# SupplyBoard.net
KiCad netlist of a schematic drawn in Altium Designer
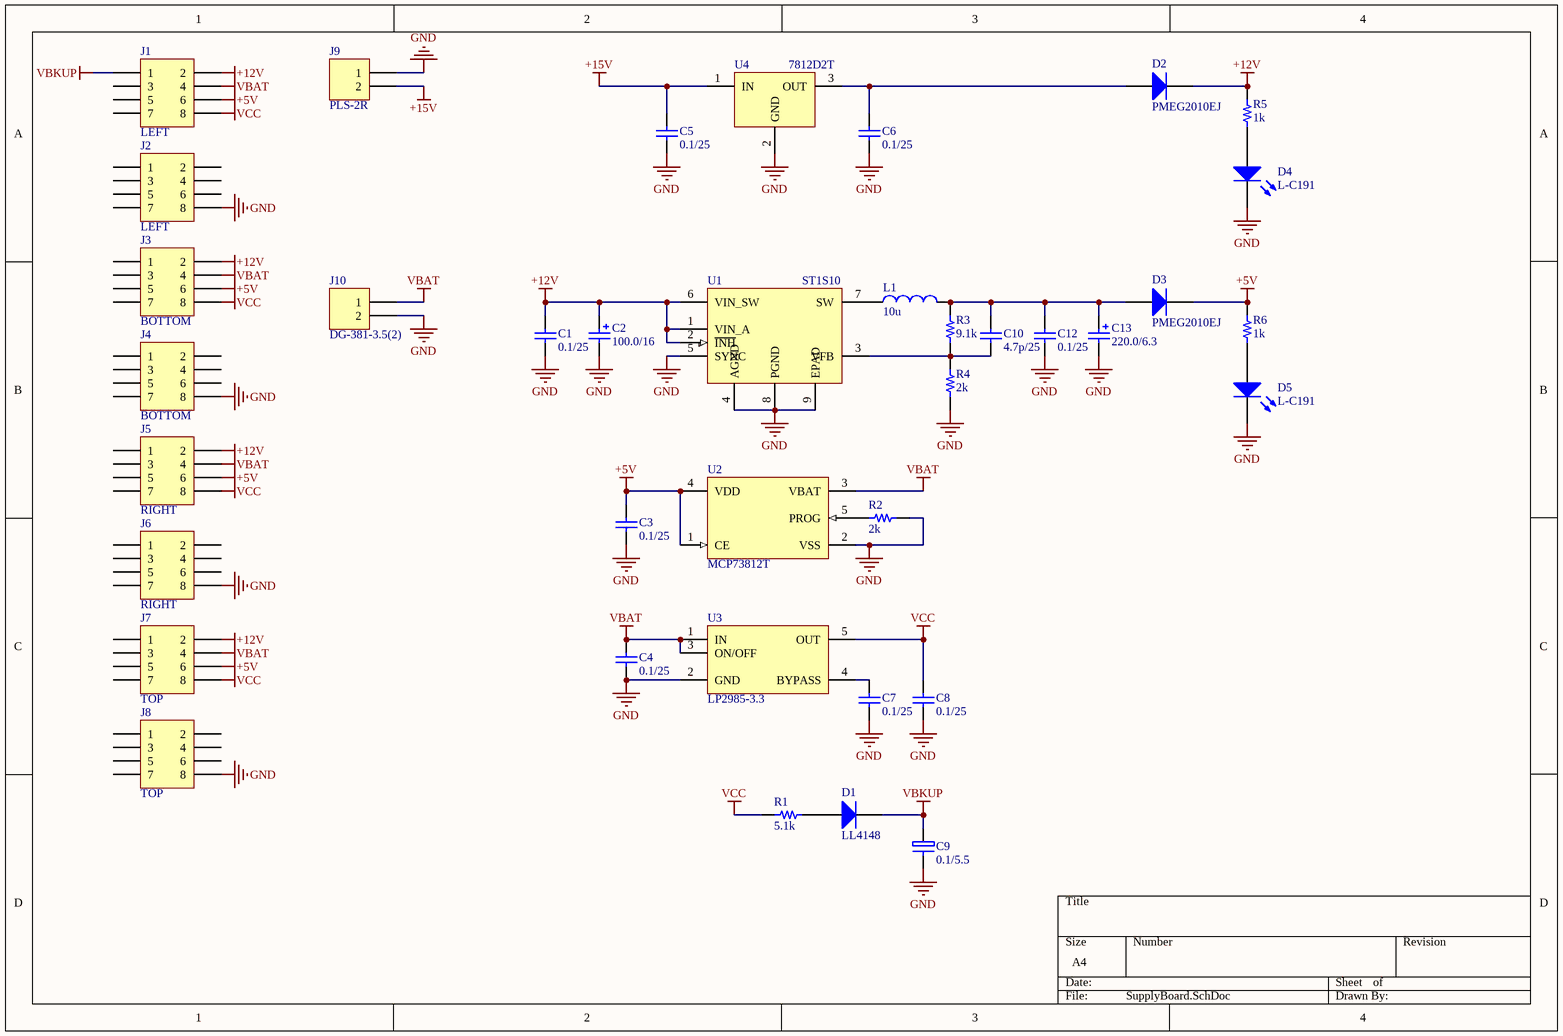
[diagram p0: SupplyBoard.SchDoc]

(export (version "E")
  (design (tool "Eeschema 10.0.6"))
  (components
    (comp (ref "C1")
      (value "0.1/25")
      (footprint "CAP0402")
      (description "Ceramic chip capacitor 0402")
      (fields
        (field (name "PARTNUMBER") "CAP0402")
        (field (name "VOLTAGE") "25")
        (field (name "AUTHOR") "oiezhov")
      )
      (libsource (lib "Library") (part "Capacitor"))
    )
    (comp (ref "C2")
      (value "100.0/16")
      (footprint "SMB")
      (description "Standard tantalum SMT capacitor, size B")
      (fields
        (field (name "PARTNUMBER") "TAJB")
        (field (name "VOLTAGE") "16")
        (field (name "AUTHOR") "oiezhov")
      )
      (libsource (lib "Library") (part "Polar capacitor"))
    )
    (comp (ref "C3")
      (value "0.1/25")
      (footprint "CAP0402")
      (description "Ceramic chip capacitor 0402")
      (fields
        (field (name "PARTNUMBER") "CAP0402")
        (field (name "VOLTAGE") "25")
        (field (name "AUTHOR") "oiezhov")
      )
      (libsource (lib "Library") (part "Capacitor"))
    )
    (comp (ref "C4")
      (value "0.1/25")
      (footprint "CAP0402")
      (description "Ceramic chip capacitor 0402")
      (fields
        (field (name "PARTNUMBER") "CAP0402")
        (field (name "VOLTAGE") "25")
        (field (name "AUTHOR") "oiezhov")
      )
      (libsource (lib "Library") (part "Capacitor"))
    )
    (comp (ref "C5")
      (value "0.1/25")
      (footprint "CAP0402")
      (description "Ceramic chip capacitor 0402")
      (fields
        (field (name "PARTNUMBER") "CAP0402")
        (field (name "VOLTAGE") "25")
        (field (name "AUTHOR") "oiezhov")
      )
      (libsource (lib "Library") (part "Capacitor"))
    )
    (comp (ref "C6")
      (value "0.1/25")
      (footprint "CAP0402")
      (description "Ceramic chip capacitor 0402")
      (fields
        (field (name "PARTNUMBER") "CAP0402")
        (field (name "VOLTAGE") "25")
        (field (name "AUTHOR") "oiezhov")
      )
      (libsource (lib "Library") (part "Capacitor"))
    )
    (comp (ref "C7")
      (value "0.1/25")
      (footprint "CAP0402")
      (description "Ceramic chip capacitor 0402")
      (fields
        (field (name "PARTNUMBER") "CAP0402")
        (field (name "VOLTAGE") "25")
        (field (name "AUTHOR") "oiezhov")
      )
      (libsource (lib "Library") (part "Capacitor"))
    )
    (comp (ref "C8")
      (value "0.1/25")
      (footprint "CAP0402")
      (description "Ceramic chip capacitor 0402")
      (fields
        (field (name "PARTNUMBER") "CAP0402")
        (field (name "VOLTAGE") "25")
        (field (name "AUTHOR") "oiezhov")
      )
      (libsource (lib "Library") (part "Capacitor"))
    )
    (comp (ref "C9")
      (value "0.1/5.5")
      (footprint "EDLC1205H")
      (description "Electric double layer capacitor")
      (fields
        (field (name "PARTNUMBER") "EDLC1205H")
        (field (name "VOLTAGE") "5.5")
        (field (name "AUTHOR") "oiezhov")
      )
      (libsource (lib "Library") (part "EDLC"))
    )
    (comp (ref "C10")
      (value "4.7p/25")
      (footprint "CAP0402")
      (description "Ceramic chip capacitor 0402")
      (fields
        (field (name "PARTNUMBER") "CAP0402")
        (field (name "VOLTAGE") "25")
        (field (name "AUTHOR") "oiezhov")
      )
      (libsource (lib "Library") (part "Capacitor"))
    )
    (comp (ref "C12")
      (value "0.1/25")
      (footprint "CAP0402")
      (description "Ceramic chip capacitor 0402")
      (fields
        (field (name "PARTNUMBER") "CAP0402")
        (field (name "VOLTAGE") "25")
        (field (name "AUTHOR") "oiezhov")
      )
      (libsource (lib "Library") (part "Capacitor"))
    )
    (comp (ref "C13")
      (value "220.0/6.3")
      (footprint "SMC")
      (description "Standard tantalum SMT capacitor, size C")
      (fields
        (field (name "PARTNUMBER") "TAJC")
        (field (name "VOLTAGE") "6.3")
        (field (name "AUTHOR") "oiezhov")
      )
      (libsource (lib "Library") (part "Polar capacitor"))
    )
    (comp (ref "D1")
      (value "LL4148")
      (footprint "SOD80")
      (description "Small Signal Diode")
      (fields (field (name "AUTHOR") "oiezhov"))
      (libsource (lib "Library") (part "Diode"))
    )
    (comp (ref "D2")
      (value "PMEG2010EJ")
      (footprint "SOD523")
      (description "1 A very low VF MEGA Schottky barrier rectifiers")
      (fields (field (name "AUTHOR") "oiezhov"))
      (libsource (lib "Library") (part "Diode"))
    )
    (comp (ref "D3")
      (value "PMEG2010EJ")
      (footprint "SOD523")
      (description "1 A very low VF MEGA Schottky barrier rectifiers")
      (fields (field (name "AUTHOR") "oiezhov"))
      (libsource (lib "Library") (part "Diode"))
    )
    (comp (ref "D4")
      (value "L-C191")
      (footprint "LED0603")
      (description "SMD LED, size 0603")
      (fields (field (name "AUTHOR") "oiezhov"))
      (libsource (lib "Library") (part "LED"))
    )
    (comp (ref "D5")
      (value "L-C191")
      (footprint "LED0603")
      (description "SMD LED, size 0603")
      (fields (field (name "AUTHOR") "oiezhov"))
      (libsource (lib "Library") (part "LED"))
    )
    (comp (ref "J1")
      (value "LEFT")
      (footprint "PBDM-8")
      (description "2x4-pin header, pitch 2.54 mm")
      (fields (field (name "PARTNUMBER") "PBDM-8") (field (name "AUTHOR") "oiezhov"))
      (libsource (lib "Library") (part "8-pin dual row connector"))
    )
    (comp (ref "J2")
      (value "LEFT")
      (footprint "PBDM-8")
      (description "2x4-pin header, pitch 2.54 mm")
      (fields (field (name "PARTNUMBER") "PBDM-8") (field (name "AUTHOR") "oiezhov"))
      (libsource (lib "Library") (part "8-pin dual row connector"))
    )
    (comp (ref "J3")
      (value "BOTTOM")
      (footprint "PBDM-8")
      (description "2x4-pin header, pitch 2.54 mm")
      (fields (field (name "PARTNUMBER") "PBDM-8") (field (name "AUTHOR") "oiezhov"))
      (libsource (lib "Library") (part "8-pin dual row connector"))
    )
    (comp (ref "J4")
      (value "BOTTOM")
      (footprint "PBDM-8")
      (description "2x4-pin header, pitch 2.54 mm")
      (fields (field (name "PARTNUMBER") "PBDM-8") (field (name "AUTHOR") "oiezhov"))
      (libsource (lib "Library") (part "8-pin dual row connector"))
    )
    (comp (ref "J5")
      (value "RIGHT")
      (footprint "PBDM-8")
      (description "2x4-pin header, pitch 2.54 mm")
      (fields (field (name "PARTNUMBER") "PBDM-8") (field (name "AUTHOR") "oiezhov"))
      (libsource (lib "Library") (part "8-pin dual row connector"))
    )
    (comp (ref "J6")
      (value "RIGHT")
      (footprint "PBDM-8")
      (description "2x4-pin header, pitch 2.54 mm")
      (fields (field (name "PARTNUMBER") "PBDM-8") (field (name "AUTHOR") "oiezhov"))
      (libsource (lib "Library") (part "8-pin dual row connector"))
    )
    (comp (ref "J7")
      (value "TOP")
      (footprint "PBDM-8")
      (description "2x4-pin header, pitch 2.54 mm")
      (fields (field (name "PARTNUMBER") "PBDM-8") (field (name "AUTHOR") "oiezhov"))
      (libsource (lib "Library") (part "8-pin dual row connector"))
    )
    (comp (ref "J8")
      (value "TOP")
      (footprint "PBDM-8")
      (description "2x4-pin header, pitch 2.54 mm")
      (fields (field (name "PARTNUMBER") "PBDM-8") (field (name "AUTHOR") "oiezhov"))
      (libsource (lib "Library") (part "8-pin dual row connector"))
    )
    (comp (ref "J9")
      (value "PLS-2R")
      (footprint "PLS-2R")
      (description "2-pin angle header, pitch 2.54 mm")
      (fields (field (name "AUTHOR") "oiezhov"))
      (libsource (lib "Library") (part "2-pin connector"))
    )
    (comp (ref "J10")
      (value "DG-381-3.5(2)")
      (footprint "DG-381-3.5(2)")
      (description "2-pin connector with screws, pitch 3.5 mm")
      (fields (field (name "AUTHOR") "oiezhov"))
      (libsource (lib "Library") (part "2-pin connector"))
    )
    (comp (ref "L1")
      (value "10u")
      (footprint "SND0705")
      (description "Power inductor")
      (fields (field (name "PARTNUMBER") "SND0705") (field (name "AUTHOR") "oiezhov"))
      (libsource (lib "Library") (part "Inductor"))
    )
    (comp (ref "R1")
      (value "5.1k")
      (footprint "RES0402")
      (description "Ceramic chip resistor")
      (fields (field (name "PARTNUMBER") "RES0402") (field (name "AUTHOR") "oiezhov"))
      (libsource (lib "Library") (part "Resistor"))
    )
    (comp (ref "R2")
      (value "2k")
      (footprint "RES0402")
      (description "Ceramic chip resistor")
      (fields (field (name "PARTNUMBER") "RES0402") (field (name "AUTHOR") "oiezhov"))
      (libsource (lib "Library") (part "Resistor"))
    )
    (comp (ref "R3")
      (value "9.1k")
      (footprint "RES0402")
      (description "Ceramic chip resistor")
      (fields (field (name "PARTNUMBER") "RES0402") (field (name "AUTHOR") "oiezhov"))
      (libsource (lib "Library") (part "Resistor"))
    )
    (comp (ref "R4")
      (value "2k")
      (footprint "RES0402")
      (description "Ceramic chip resistor")
      (fields (field (name "PARTNUMBER") "RES0402") (field (name "AUTHOR") "oiezhov"))
      (libsource (lib "Library") (part "Resistor"))
    )
    (comp (ref "R5")
      (value "1k")
      (footprint "RES0402")
      (description "Ceramic chip resistor")
      (fields (field (name "PARTNUMBER") "RES0402") (field (name "AUTHOR") "oiezhov"))
      (libsource (lib "Library") (part "Resistor"))
    )
    (comp (ref "R6")
      (value "1k")
      (footprint "RES0402")
      (description "Ceramic chip resistor")
      (fields (field (name "PARTNUMBER") "RES0402") (field (name "AUTHOR") "oiezhov"))
      (libsource (lib "Library") (part "Resistor"))
    )
    (comp (ref "U1")
      (value "ST1S10")
      (footprint "PowerSO8")
      (description "DC-DC buck converter")
      (fields (field (name "AUTHOR") "oiezhov"))
      (libsource (lib "Library") (part "ST1S10"))
    )
    (comp (ref "U2")
      (value "MCP73812T")
      (footprint "SOT23-5")
      (description "Li-Ion/Li-Po battery charge management controller")
      (fields (field (name "AUTHOR") "oiezhov"))
      (libsource (lib "Library") (part "MCP73812"))
    )
    (comp (ref "U3")
      (value "LP2985-3.3")
      (footprint "SOT23-5")
      (description "Micropower 150 mA Low-Noise Ultra Low-Dropout Regulator")
      (fields (field (name "AUTHOR") "oiezhov"))
      (libsource (lib "Library") (part "5-pin voltage regulator with ON/OFF and BYPASS"))
    )
    (comp (ref "U4")
      (value "7812D2T")
      (footprint "D2PAK-3")
      (description "1.0 A Positive Voltage Regulator")
      (fields (field (name "AUTHOR") "oiezhov"))
      (libsource (lib "Library") (part "3-pin voltage regulator"))
    )
  )
  (nets
    (net (code "1") (name "+5V") (class "Default")
      (node (ref "C3") (pin "2") (pinfunction "2_2") (pintype "passive"))
      (node (ref "D3") (pin "1") (pinfunction "1_1") (pintype "passive"))
      (node (ref "J1") (pin "6") (pinfunction "6_6") (pintype "passive"))
      (node (ref "J3") (pin "6") (pinfunction "6_6") (pintype "passive"))
      (node (ref "J5") (pin "6") (pinfunction "6_6") (pintype "passive"))
      (node (ref "J7") (pin "6") (pinfunction "6_6") (pintype "passive"))
      (node (ref "R6") (pin "2") (pinfunction "2_2") (pintype "passive"))
      (node (ref "U2") (pin "1") (pinfunction "CE_1") (pintype "input"))
      (node (ref "U2") (pin "4") (pinfunction "VDD_4") (pintype "power_in"))
    )
    (net (code "2") (name "+12V") (class "Default")
      (node (ref "C1") (pin "2") (pinfunction "2_2") (pintype "passive"))
      (node (ref "C2") (pin "2") (pinfunction "2_2") (pintype "passive"))
      (node (ref "D2") (pin "1") (pinfunction "1_1") (pintype "passive"))
      (node (ref "J1") (pin "2") (pinfunction "2_2") (pintype "passive"))
      (node (ref "J3") (pin "2") (pinfunction "2_2") (pintype "passive"))
      (node (ref "J5") (pin "2") (pinfunction "2_2") (pintype "passive"))
      (node (ref "J7") (pin "2") (pinfunction "2_2") (pintype "passive"))
      (node (ref "R5") (pin "2") (pinfunction "2_2") (pintype "passive"))
      (node (ref "U1") (pin "1") (pinfunction "VIN_A_1") (pintype "power_in"))
      (node (ref "U1") (pin "2") (pinfunction "~{INH}_2") (pintype "input"))
      (node (ref "U1") (pin "6") (pinfunction "VIN_SW_6") (pintype "power_in"))
    )
    (net (code "3") (name "+15V") (class "Default")
      (node (ref "C5") (pin "2") (pinfunction "2_2") (pintype "passive"))
      (node (ref "J9") (pin "2") (pinfunction "2_2") (pintype "passive"))
      (node (ref "U4") (pin "1") (pinfunction "IN_1") (pintype "passive"))
    )
    (net (code "4") (name "GND") (class "Default")
      (node (ref "C1") (pin "1") (pinfunction "1_1") (pintype "passive"))
      (node (ref "C12") (pin "1") (pinfunction "1_1") (pintype "passive"))
      (node (ref "C13") (pin "1") (pinfunction "1_1") (pintype "passive"))
      (node (ref "C2") (pin "1") (pinfunction "1_1") (pintype "passive"))
      (node (ref "C3") (pin "1") (pinfunction "1_1") (pintype "passive"))
      (node (ref "C4") (pin "1") (pinfunction "1_1") (pintype "passive"))
      (node (ref "C5") (pin "1") (pinfunction "1_1") (pintype "passive"))
      (node (ref "C6") (pin "1") (pinfunction "1_1") (pintype "passive"))
      (node (ref "C7") (pin "1") (pinfunction "1_1") (pintype "passive"))
      (node (ref "C8") (pin "1") (pinfunction "1_1") (pintype "passive"))
      (node (ref "C9") (pin "1") (pinfunction "1_1") (pintype "passive"))
      (node (ref "D4") (pin "1") (pinfunction "1_1") (pintype "passive"))
      (node (ref "D5") (pin "1") (pinfunction "1_1") (pintype "passive"))
      (node (ref "J10") (pin "2") (pinfunction "2_2") (pintype "passive"))
      (node (ref "J2") (pin "8") (pinfunction "8_8") (pintype "passive"))
      (node (ref "J4") (pin "8") (pinfunction "8_8") (pintype "passive"))
      (node (ref "J6") (pin "8") (pinfunction "8_8") (pintype "passive"))
      (node (ref "J8") (pin "8") (pinfunction "8_8") (pintype "passive"))
      (node (ref "J9") (pin "1") (pinfunction "1_1") (pintype "passive"))
      (node (ref "R2") (pin "1") (pinfunction "1_1") (pintype "passive"))
      (node (ref "R4") (pin "1") (pinfunction "1_1") (pintype "passive"))
      (node (ref "U1") (pin "4") (pinfunction "AGND_4") (pintype "power_in"))
      (node (ref "U1") (pin "5") (pinfunction "SYNC_5") (pintype "passive"))
      (node (ref "U1") (pin "8") (pinfunction "PGND_8") (pintype "power_in"))
      (node (ref "U1") (pin "9") (pinfunction "EPAD_9") (pintype "power_in"))
      (node (ref "U2") (pin "2") (pinfunction "VSS_2") (pintype "power_in"))
      (node (ref "U3") (pin "2") (pinfunction "GND_2") (pintype "passive"))
      (node (ref "U4") (pin "2") (pinfunction "GND_2") (pintype "passive"))
    )
    (net (code "5") (name "Net-(C10-Pad2)") (class "Default")
      (node (ref "C10") (pin "2") (pinfunction "2_2") (pintype "passive"))
      (node (ref "C12") (pin "2") (pinfunction "2_2") (pintype "passive"))
      (node (ref "C13") (pin "2") (pinfunction "2_2") (pintype "passive"))
      (node (ref "D3") (pin "2") (pinfunction "2_2") (pintype "passive"))
      (node (ref "L1") (pin "2") (pinfunction "2_2") (pintype "passive"))
      (node (ref "R3") (pin "2") (pinfunction "2_2") (pintype "passive"))
    )
    (net (code "6") (name "Net-(D1-Pad2)") (class "Default")
      (node (ref "D1") (pin "2") (pinfunction "2_2") (pintype "passive"))
      (node (ref "R1") (pin "1") (pinfunction "1_1") (pintype "passive"))
    )
    (net (code "7") (name "Net-(D4-Pad2)") (class "Default")
      (node (ref "D4") (pin "2") (pinfunction "2_2") (pintype "passive"))
      (node (ref "R5") (pin "1") (pinfunction "1_1") (pintype "passive"))
    )
    (net (code "8") (name "Net-(D5-Pad2)") (class "Default")
      (node (ref "D5") (pin "2") (pinfunction "2_2") (pintype "passive"))
      (node (ref "R6") (pin "1") (pinfunction "1_1") (pintype "passive"))
    )
    (net (code "9") (name "Net-(U1-SW)") (class "Default")
      (node (ref "L1") (pin "1") (pinfunction "1_1") (pintype "passive"))
      (node (ref "U1") (pin "7") (pinfunction "SW_7") (pintype "power_in"))
    )
    (net (code "10") (name "Net-(U1-VFB)") (class "Default")
      (node (ref "C10") (pin "1") (pinfunction "1_1") (pintype "passive"))
      (node (ref "R3") (pin "1") (pinfunction "1_1") (pintype "passive"))
      (node (ref "R4") (pin "2") (pinfunction "2_2") (pintype "passive"))
      (node (ref "U1") (pin "3") (pinfunction "VFB_3") (pintype "passive"))
    )
    (net (code "11") (name "Net-(U2-PROG)") (class "Default")
      (node (ref "R2") (pin "2") (pinfunction "2_2") (pintype "passive"))
      (node (ref "U2") (pin "5") (pinfunction "PROG_5") (pintype "input"))
    )
    (net (code "12") (name "Net-(U3-BYPASS)") (class "Default")
      (node (ref "C7") (pin "2") (pinfunction "2_2") (pintype "passive"))
      (node (ref "U3") (pin "4") (pinfunction "BYPASS_4") (pintype "passive"))
    )
    (net (code "13") (name "Net-(U4-OUT)") (class "Default")
      (node (ref "C6") (pin "2") (pinfunction "2_2") (pintype "passive"))
      (node (ref "D2") (pin "2") (pinfunction "2_2") (pintype "passive"))
      (node (ref "U4") (pin "3") (pinfunction "OUT_3") (pintype "passive"))
    )
    (net (code "14") (name "VBAT") (class "Default")
      (node (ref "C4") (pin "2") (pinfunction "2_2") (pintype "passive"))
      (node (ref "J1") (pin "4") (pinfunction "4_4") (pintype "passive"))
      (node (ref "J10") (pin "1") (pinfunction "1_1") (pintype "passive"))
      (node (ref "J3") (pin "4") (pinfunction "4_4") (pintype "passive"))
      (node (ref "J5") (pin "4") (pinfunction "4_4") (pintype "passive"))
      (node (ref "J7") (pin "4") (pinfunction "4_4") (pintype "passive"))
      (node (ref "U2") (pin "3") (pinfunction "VBAT_3") (pintype "power_in"))
      (node (ref "U3") (pin "1") (pinfunction "IN_1") (pintype "passive"))
      (node (ref "U3") (pin "3") (pinfunction "ON/OFF_3") (pintype "passive"))
    )
    (net (code "15") (name "VBKUP") (class "Default")
      (node (ref "C9") (pin "2") (pinfunction "2_2") (pintype "passive"))
      (node (ref "D1") (pin "1") (pinfunction "1_1") (pintype "passive"))
      (node (ref "J1") (pin "1") (pinfunction "1_1") (pintype "passive"))
    )
    (net (code "16") (name "VCC") (class "Default")
      (node (ref "C8") (pin "2") (pinfunction "2_2") (pintype "passive"))
      (node (ref "J1") (pin "8") (pinfunction "8_8") (pintype "passive"))
      (node (ref "J3") (pin "8") (pinfunction "8_8") (pintype "passive"))
      (node (ref "J5") (pin "8") (pinfunction "8_8") (pintype "passive"))
      (node (ref "J7") (pin "8") (pinfunction "8_8") (pintype "passive"))
      (node (ref "R1") (pin "2") (pinfunction "2_2") (pintype "passive"))
      (node (ref "U3") (pin "5") (pinfunction "OUT_5") (pintype "passive"))
    )
    (net (code "17") (name "unconnected-(J1-Pad3)") (class "Default")
      (node (ref "J1") (pin "3") (pinfunction "3_3") (pintype "passive"))
    )
    (net (code "18") (name "unconnected-(J1-Pad5)") (class "Default")
      (node (ref "J1") (pin "5") (pinfunction "5_5") (pintype "passive"))
    )
    (net (code "19") (name "unconnected-(J1-Pad7)") (class "Default")
      (node (ref "J1") (pin "7") (pinfunction "7_7") (pintype "passive"))
    )
    (net (code "20") (name "unconnected-(J2-Pad1)") (class "Default")
      (node (ref "J2") (pin "1") (pinfunction "1_1") (pintype "passive"))
    )
    (net (code "21") (name "unconnected-(J2-Pad2)") (class "Default")
      (node (ref "J2") (pin "2") (pinfunction "2_2") (pintype "passive"))
    )
    (net (code "22") (name "unconnected-(J2-Pad3)") (class "Default")
      (node (ref "J2") (pin "3") (pinfunction "3_3") (pintype "passive"))
    )
    (net (code "23") (name "unconnected-(J2-Pad4)") (class "Default")
      (node (ref "J2") (pin "4") (pinfunction "4_4") (pintype "passive"))
    )
    (net (code "24") (name "unconnected-(J2-Pad5)") (class "Default")
      (node (ref "J2") (pin "5") (pinfunction "5_5") (pintype "passive"))
    )
    (net (code "25") (name "unconnected-(J2-Pad6)") (class "Default")
      (node (ref "J2") (pin "6") (pinfunction "6_6") (pintype "passive"))
    )
    (net (code "26") (name "unconnected-(J2-Pad7)") (class "Default")
      (node (ref "J2") (pin "7") (pinfunction "7_7") (pintype "passive"))
    )
    (net (code "27") (name "unconnected-(J3-Pad1)") (class "Default")
      (node (ref "J3") (pin "1") (pinfunction "1_1") (pintype "passive"))
    )
    (net (code "28") (name "unconnected-(J3-Pad3)") (class "Default")
      (node (ref "J3") (pin "3") (pinfunction "3_3") (pintype "passive"))
    )
    (net (code "29") (name "unconnected-(J3-Pad5)") (class "Default")
      (node (ref "J3") (pin "5") (pinfunction "5_5") (pintype "passive"))
    )
    (net (code "30") (name "unconnected-(J3-Pad7)") (class "Default")
      (node (ref "J3") (pin "7") (pinfunction "7_7") (pintype "passive"))
    )
    (net (code "31") (name "unconnected-(J4-Pad1)") (class "Default")
      (node (ref "J4") (pin "1") (pinfunction "1_1") (pintype "passive"))
    )
    (net (code "32") (name "unconnected-(J4-Pad2)") (class "Default")
      (node (ref "J4") (pin "2") (pinfunction "2_2") (pintype "passive"))
    )
    (net (code "33") (name "unconnected-(J4-Pad3)") (class "Default")
      (node (ref "J4") (pin "3") (pinfunction "3_3") (pintype "passive"))
    )
    (net (code "34") (name "unconnected-(J4-Pad4)") (class "Default")
      (node (ref "J4") (pin "4") (pinfunction "4_4") (pintype "passive"))
    )
    (net (code "35") (name "unconnected-(J4-Pad5)") (class "Default")
      (node (ref "J4") (pin "5") (pinfunction "5_5") (pintype "passive"))
    )
    (net (code "36") (name "unconnected-(J4-Pad6)") (class "Default")
      (node (ref "J4") (pin "6") (pinfunction "6_6") (pintype "passive"))
    )
    (net (code "37") (name "unconnected-(J4-Pad7)") (class "Default")
      (node (ref "J4") (pin "7") (pinfunction "7_7") (pintype "passive"))
    )
    (net (code "38") (name "unconnected-(J5-Pad1)") (class "Default")
      (node (ref "J5") (pin "1") (pinfunction "1_1") (pintype "passive"))
    )
    (net (code "39") (name "unconnected-(J5-Pad3)") (class "Default")
      (node (ref "J5") (pin "3") (pinfunction "3_3") (pintype "passive"))
    )
    (net (code "40") (name "unconnected-(J5-Pad5)") (class "Default")
      (node (ref "J5") (pin "5") (pinfunction "5_5") (pintype "passive"))
    )
    (net (code "41") (name "unconnected-(J5-Pad7)") (class "Default")
      (node (ref "J5") (pin "7") (pinfunction "7_7") (pintype "passive"))
    )
    (net (code "42") (name "unconnected-(J6-Pad1)") (class "Default")
      (node (ref "J6") (pin "1") (pinfunction "1_1") (pintype "passive"))
    )
    (net (code "43") (name "unconnected-(J6-Pad2)") (class "Default")
      (node (ref "J6") (pin "2") (pinfunction "2_2") (pintype "passive"))
    )
    (net (code "44") (name "unconnected-(J6-Pad3)") (class "Default")
      (node (ref "J6") (pin "3") (pinfunction "3_3") (pintype "passive"))
    )
    (net (code "45") (name "unconnected-(J6-Pad4)") (class "Default")
      (node (ref "J6") (pin "4") (pinfunction "4_4") (pintype "passive"))
    )
    (net (code "46") (name "unconnected-(J6-Pad5)") (class "Default")
      (node (ref "J6") (pin "5") (pinfunction "5_5") (pintype "passive"))
    )
    (net (code "47") (name "unconnected-(J6-Pad6)") (class "Default")
      (node (ref "J6") (pin "6") (pinfunction "6_6") (pintype "passive"))
    )
    (net (code "48") (name "unconnected-(J6-Pad7)") (class "Default")
      (node (ref "J6") (pin "7") (pinfunction "7_7") (pintype "passive"))
    )
    (net (code "49") (name "unconnected-(J7-Pad1)") (class "Default")
      (node (ref "J7") (pin "1") (pinfunction "1_1") (pintype "passive"))
    )
    (net (code "50") (name "unconnected-(J7-Pad3)") (class "Default")
      (node (ref "J7") (pin "3") (pinfunction "3_3") (pintype "passive"))
    )
    (net (code "51") (name "unconnected-(J7-Pad5)") (class "Default")
      (node (ref "J7") (pin "5") (pinfunction "5_5") (pintype "passive"))
    )
    (net (code "52") (name "unconnected-(J7-Pad7)") (class "Default")
      (node (ref "J7") (pin "7") (pinfunction "7_7") (pintype "passive"))
    )
    (net (code "53") (name "unconnected-(J8-Pad1)") (class "Default")
      (node (ref "J8") (pin "1") (pinfunction "1_1") (pintype "passive"))
    )
    (net (code "54") (name "unconnected-(J8-Pad2)") (class "Default")
      (node (ref "J8") (pin "2") (pinfunction "2_2") (pintype "passive"))
    )
    (net (code "55") (name "unconnected-(J8-Pad3)") (class "Default")
      (node (ref "J8") (pin "3") (pinfunction "3_3") (pintype "passive"))
    )
    (net (code "56") (name "unconnected-(J8-Pad4)") (class "Default")
      (node (ref "J8") (pin "4") (pinfunction "4_4") (pintype "passive"))
    )
    (net (code "57") (name "unconnected-(J8-Pad5)") (class "Default")
      (node (ref "J8") (pin "5") (pinfunction "5_5") (pintype "passive"))
    )
    (net (code "58") (name "unconnected-(J8-Pad6)") (class "Default")
      (node (ref "J8") (pin "6") (pinfunction "6_6") (pintype "passive"))
    )
    (net (code "59") (name "unconnected-(J8-Pad7)") (class "Default")
      (node (ref "J8") (pin "7") (pinfunction "7_7") (pintype "passive"))
    )
  )
)
